# assignment.net
KiCad netlist of a schematic drawn in EAGLE
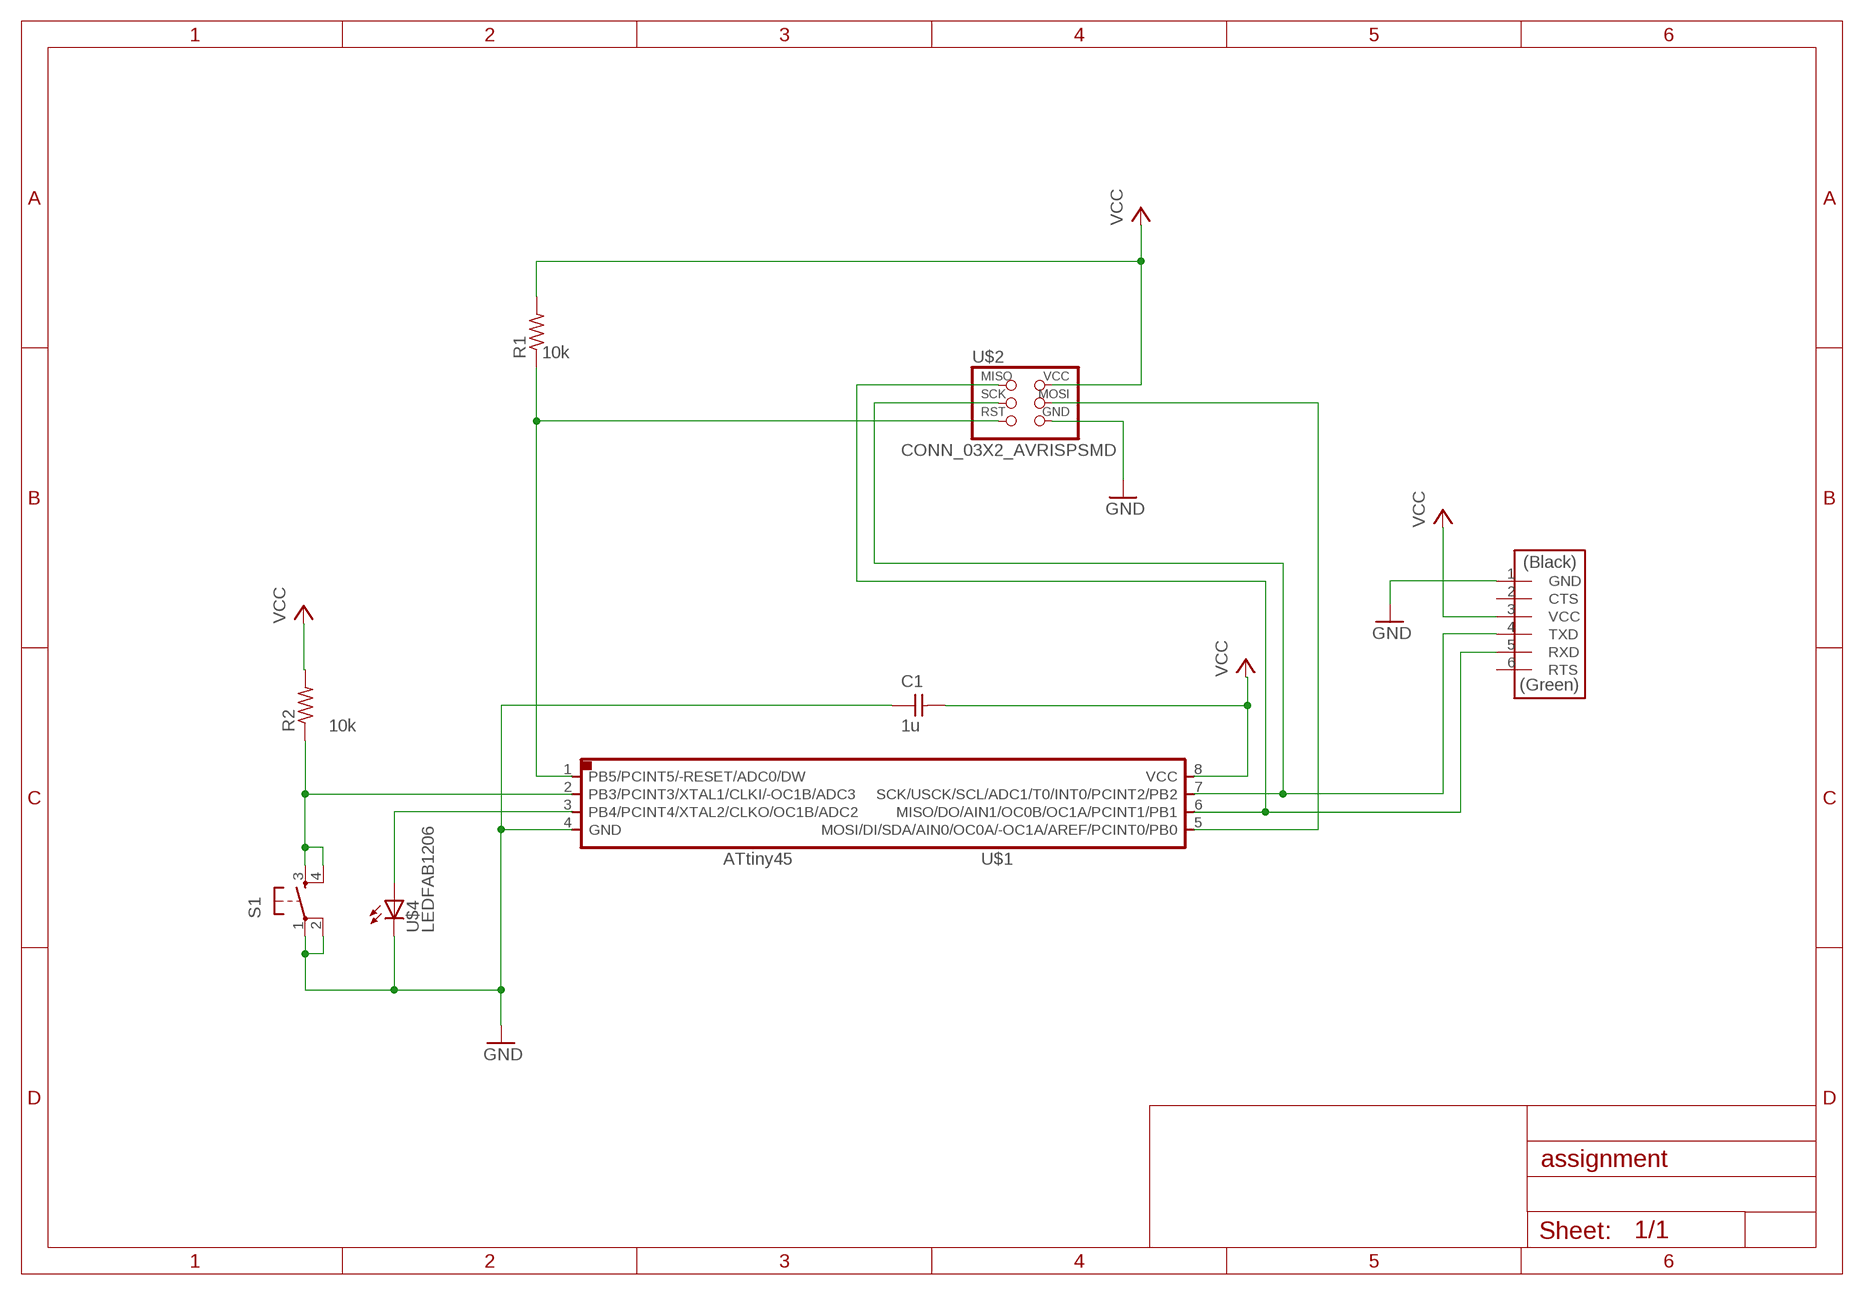
[diagram p0: schematic, sheet 1]

(export (version "E")
  (design (tool "Eeschema 10.0.6"))
  (components
    (comp (ref "C1")
      (value "1u")
      (footprint "eagle-import:C1206FAB")
      (libsource (lib "eagle-import") (part "CAP_UNPOLARIZEDFAB"))
    )
    (comp (ref "R1")
      (value "10k")
      (footprint "eagle-import:R1206FAB")
      (libsource (lib "eagle-import") (part "R1206FAB"))
    )
    (comp (ref "R2")
      (value "10k")
      (footprint "eagle-import:R1206FAB")
      (libsource (lib "eagle-import") (part "R1206FAB"))
    )
    (comp (ref "S1")
      (value "SW_SWITCH_TACTILE_6MM6MM_SWITCH")
      (footprint "eagle-import:6MM_SWITCH")
      (libsource (lib "eagle-import") (part "SW_SWITCH_TACTILE_6MM6MM_SWITCH"))
    )
    (comp (ref "U$1")
      (value "UC_ATTINY45SI")
      (footprint "eagle-import:SOIC8")
      (libsource (lib "eagle-import") (part "UC_ATTINY45SI"))
    )
    (comp (ref "U$2")
      (value "CONN_03X2_AVRISPSMD")
      (footprint "eagle-import:2X03SMD")
      (libsource (lib "eagle-import") (part "CONN_03X2_AVRISPSMD"))
    )
    (comp (ref "U$3")
      (value "CONN_06_FTDI-SMD-HEADER")
      (footprint "eagle-import:1X06SMD")
      (libsource (lib "eagle-import") (part "CONN_06_FTDI-SMD-HEADER"))
    )
    (comp (ref "U$4")
      (value "LEDFAB1206")
      (footprint "eagle-import:LED1206FAB")
      (libsource (lib "eagle-import") (part "LEDFAB1206"))
    )
  )
  (nets
    (net (code "1") (name "GND") (class "Default")
      (node (ref "C1") (pin "1") (pinfunction "1_1") (pintype "passive"))
      (node (ref "S1") (pin "1") (pinfunction "P_1") (pintype "passive"))
      (node (ref "S1") (pin "2") (pinfunction "P1_2") (pintype "passive"))
      (node (ref "U$1") (pin "4") (pinfunction "GND_4") (pintype "bidirectional"))
      (node (ref "U$2") (pin "6") (pinfunction "GND_6") (pintype "passive"))
      (node (ref "U$3") (pin "1") (pinfunction "GND_1") (pintype "bidirectional"))
      (node (ref "U$4") (pin "2") (pinfunction "C_2") (pintype "passive"))
    )
    (net (code "2") (name "Net-(S1-S)") (class "Default")
      (node (ref "R2") (pin "1") (pinfunction "1_1") (pintype "passive"))
      (node (ref "S1") (pin "3") (pinfunction "S_3") (pintype "passive"))
      (node (ref "S1") (pin "4") (pinfunction "S1_4") (pintype "passive"))
      (node (ref "U$1") (pin "2") (pinfunction "PB3/PCINT3/XTAL1/CLKI/-OC1B/ADC3_2") (pintype "bidirectional"))
    )
    (net (code "3") (name "Net-(U$1-MISO{slash}DO{slash}AIN1{slash}OC0B{slash}OC1A{slash}PCINT1{slash}PB1)") (class "Default")
      (node (ref "U$1") (pin "6") (pinfunction "MISO/DO/AIN1/OC0B/OC1A/PCINT1/PB1_6") (pintype "bidirectional"))
      (node (ref "U$2") (pin "1") (pinfunction "MISO_1") (pintype "passive"))
      (node (ref "U$3") (pin "5") (pinfunction "RXD_5") (pintype "bidirectional"))
    )
    (net (code "4") (name "Net-(U$1-MOSI{slash}DI{slash}SDA{slash}AIN0{slash}OC0A{slash}-OC1A{slash}AREF{slash}PCINT0{slash}PB0)") (class "Default")
      (node (ref "U$1") (pin "5") (pinfunction "MOSI/DI/SDA/AIN0/OC0A/-OC1A/AREF/PCINT0/PB0_5") (pintype "bidirectional"))
      (node (ref "U$2") (pin "4") (pinfunction "MOSI_4") (pintype "passive"))
    )
    (net (code "5") (name "Net-(U$1-PB4{slash}PCINT4{slash}XTAL2{slash}CLKO{slash}OC1B{slash}ADC2)") (class "Default")
      (node (ref "U$1") (pin "3") (pinfunction "PB4/PCINT4/XTAL2/CLKO/OC1B/ADC2_3") (pintype "bidirectional"))
      (node (ref "U$4") (pin "1") (pinfunction "A_1") (pintype "passive"))
    )
    (net (code "6") (name "Net-(U$1-PB5{slash}PCINT5{slash}-RESET{slash}ADC0{slash}DW)") (class "Default")
      (node (ref "R1") (pin "1") (pinfunction "1_1") (pintype "passive"))
      (node (ref "U$1") (pin "1") (pinfunction "PB5/PCINT5/-RESET/ADC0/DW_1") (pintype "bidirectional"))
      (node (ref "U$2") (pin "5") (pinfunction "RST_5") (pintype "passive"))
    )
    (net (code "7") (name "Net-(U$1-SCK{slash}USCK{slash}SCL{slash}ADC1{slash}T0{slash}INT0{slash}PCINT2{slash}PB2)") (class "Default")
      (node (ref "U$1") (pin "7") (pinfunction "SCK/USCK/SCL/ADC1/T0/INT0/PCINT2/PB2_7") (pintype "bidirectional"))
      (node (ref "U$2") (pin "3") (pinfunction "SCK_3") (pintype "passive"))
      (node (ref "U$3") (pin "4") (pinfunction "TXD_4") (pintype "bidirectional"))
    )
    (net (code "8") (name "VCC") (class "Default")
      (node (ref "C1") (pin "2") (pinfunction "2_2") (pintype "passive"))
      (node (ref "R1") (pin "2") (pinfunction "2_2") (pintype "passive"))
      (node (ref "R2") (pin "2") (pinfunction "2_2") (pintype "passive"))
      (node (ref "U$1") (pin "8") (pinfunction "VCC_8") (pintype "bidirectional"))
      (node (ref "U$2") (pin "2") (pinfunction "VCC_2") (pintype "passive"))
      (node (ref "U$3") (pin "3") (pinfunction "VCC_3") (pintype "bidirectional"))
    )
    (net (code "9") (name "unconnected-(U$3-CTS-Pad2)") (class "Default")
      (node (ref "U$3") (pin "2") (pinfunction "CTS_2") (pintype "bidirectional"))
    )
    (net (code "10") (name "unconnected-(U$3-RTS-Pad6)") (class "Default")
      (node (ref "U$3") (pin "6") (pinfunction "RTS_6") (pintype "bidirectional"))
    )
  )
)
